# SingleSide.net
KiCad netlist of a schematic drawn in EAGLE
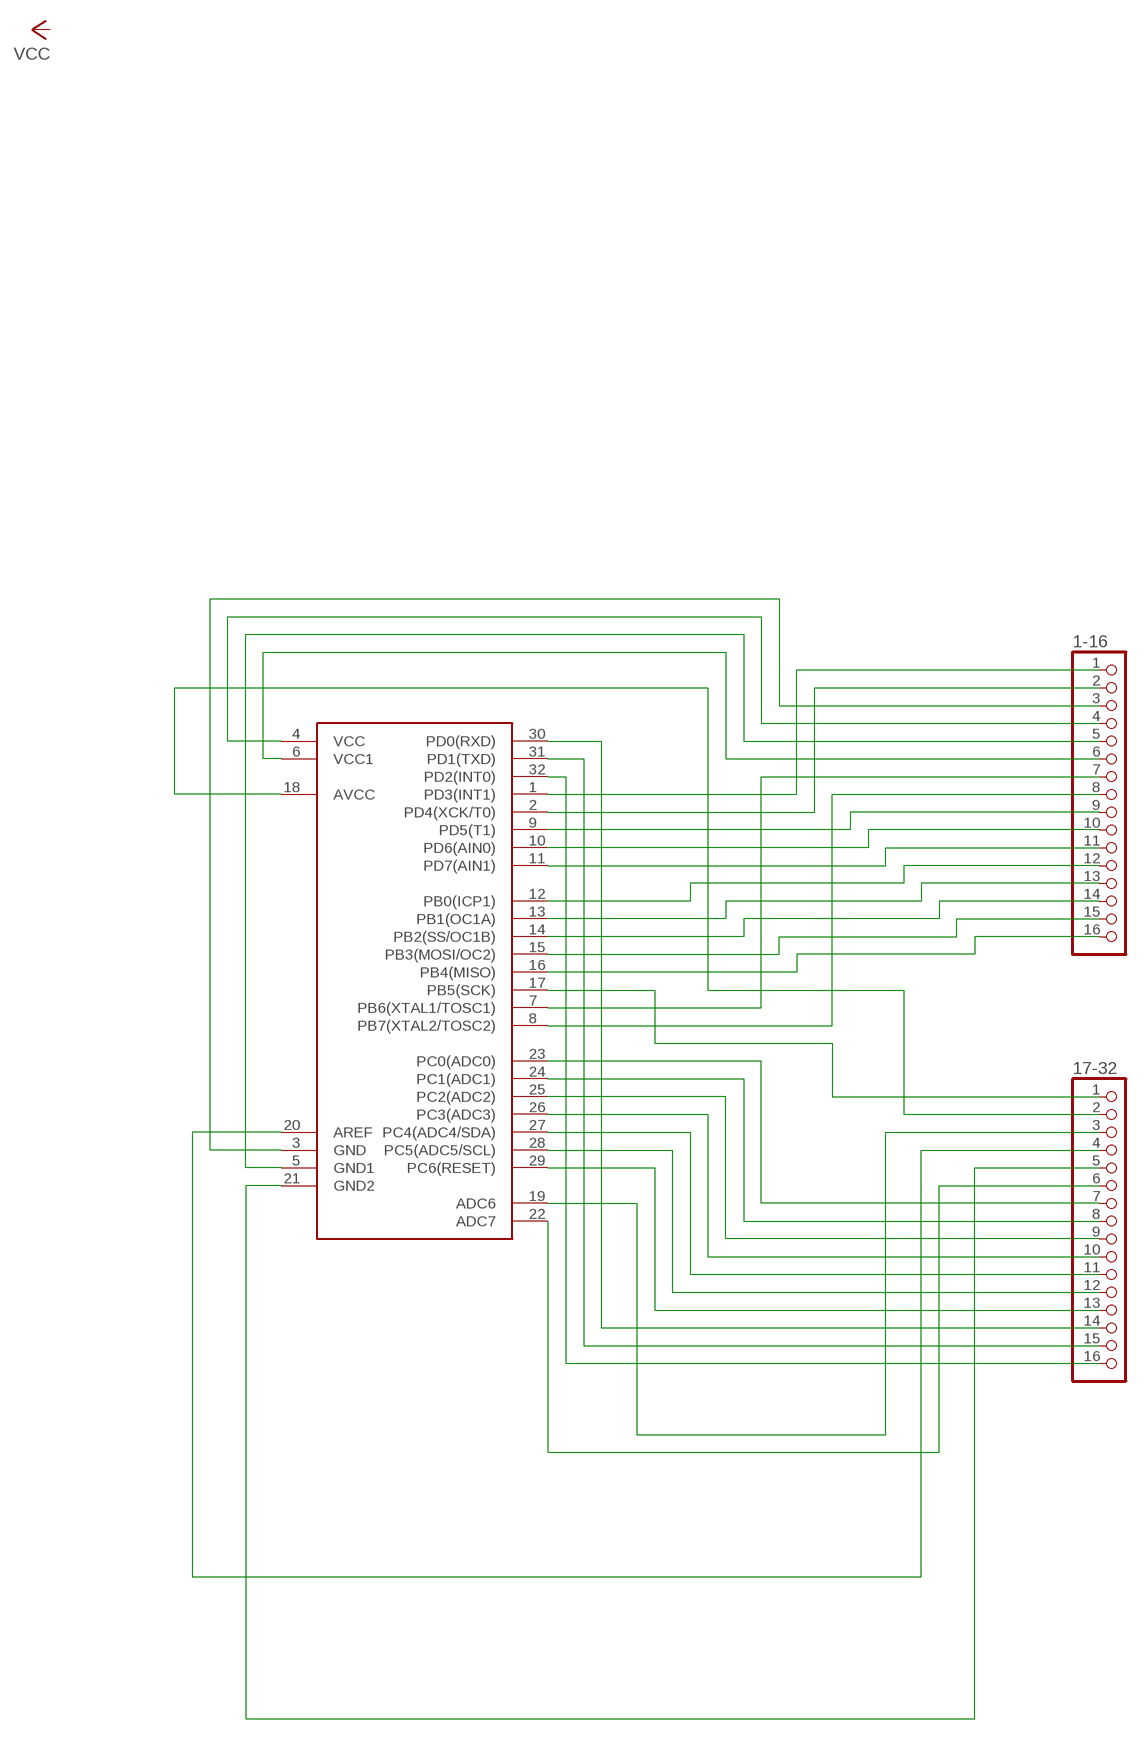
[diagram p0: schematic, sheet 1]

(export (version "E")
  (design (tool "Eeschema 10.0.6"))
  (components
    (comp (ref "1-16")
      (value "PINHD-1X16")
      (footprint "eagle-import:1X16")
      (libsource (lib "eagle-import") (part "PINHD-1X16"))
    )
    (comp (ref "17-32")
      (value "PINHD-1X16")
      (footprint "eagle-import:1X16")
      (libsource (lib "eagle-import") (part "PINHD-1X16"))
    )
    (comp (ref "U$1")
      (value "ATMEGA8A")
      (footprint "eagle-import:TQFP32-08")
      (libsource (lib "eagle-import") (part "ATMEGA8A"))
    )
  )
  (nets
    (net (code "1") (name "Net-(U$1-ADC6)") (class "Default")
      (node (ref "17-32") (pin "3") (pinfunction "3_3") (pintype "passive"))
      (node (ref "U$1") (pin "19") (pinfunction "ADC6_19") (pintype "bidirectional"))
    )
    (net (code "2") (name "Net-(U$1-ADC7)") (class "Default")
      (node (ref "17-32") (pin "6") (pinfunction "6_6") (pintype "passive"))
      (node (ref "U$1") (pin "22") (pinfunction "ADC7_22") (pintype "bidirectional"))
    )
    (net (code "3") (name "Net-(U$1-AREF)") (class "Default")
      (node (ref "17-32") (pin "4") (pinfunction "4_4") (pintype "passive"))
      (node (ref "U$1") (pin "20") (pinfunction "AREF_20") (pintype "bidirectional"))
    )
    (net (code "4") (name "Net-(U$1-AVCC)") (class "Default")
      (node (ref "17-32") (pin "2") (pinfunction "2_2") (pintype "passive"))
      (node (ref "U$1") (pin "18") (pinfunction "AVCC_18") (pintype "bidirectional"))
    )
    (net (code "5") (name "Net-(U$1-GND)") (class "Default")
      (node (ref "1-16") (pin "3") (pinfunction "3_3") (pintype "passive"))
      (node (ref "U$1") (pin "3") (pinfunction "GND_3") (pintype "bidirectional"))
    )
    (net (code "6") (name "Net-(U$1-GND1)") (class "Default")
      (node (ref "1-16") (pin "5") (pinfunction "5_5") (pintype "passive"))
      (node (ref "U$1") (pin "5") (pinfunction "GND1_5") (pintype "bidirectional"))
    )
    (net (code "7") (name "Net-(U$1-GND2)") (class "Default")
      (node (ref "17-32") (pin "5") (pinfunction "5_5") (pintype "passive"))
      (node (ref "U$1") (pin "21") (pinfunction "GND2_21") (pintype "bidirectional"))
    )
    (net (code "8") (name "Net-(U$1-PB0(ICP1))") (class "Default")
      (node (ref "1-16") (pin "12") (pinfunction "12_12") (pintype "passive"))
      (node (ref "U$1") (pin "12") (pinfunction "PB0(ICP1)_12") (pintype "bidirectional"))
    )
    (net (code "9") (name "Net-(U$1-PB1(OC1A))") (class "Default")
      (node (ref "1-16") (pin "13") (pinfunction "13_13") (pintype "passive"))
      (node (ref "U$1") (pin "13") (pinfunction "PB1(OC1A)_13") (pintype "bidirectional"))
    )
    (net (code "10") (name "Net-(U$1-PB2(SS{slash}OC1B))") (class "Default")
      (node (ref "1-16") (pin "14") (pinfunction "14_14") (pintype "passive"))
      (node (ref "U$1") (pin "14") (pinfunction "PB2(SS/OC1B)_14") (pintype "bidirectional"))
    )
    (net (code "11") (name "Net-(U$1-PB3(MOSI{slash}OC2))") (class "Default")
      (node (ref "1-16") (pin "15") (pinfunction "15_15") (pintype "passive"))
      (node (ref "U$1") (pin "15") (pinfunction "PB3(MOSI/OC2)_15") (pintype "bidirectional"))
    )
    (net (code "12") (name "Net-(U$1-PB4(MISO))") (class "Default")
      (node (ref "1-16") (pin "16") (pinfunction "16_16") (pintype "passive"))
      (node (ref "U$1") (pin "16") (pinfunction "PB4(MISO)_16") (pintype "bidirectional"))
    )
    (net (code "13") (name "Net-(U$1-PB5(SCK))") (class "Default")
      (node (ref "17-32") (pin "1") (pinfunction "1_1") (pintype "passive"))
      (node (ref "U$1") (pin "17") (pinfunction "PB5(SCK)_17") (pintype "bidirectional"))
    )
    (net (code "14") (name "Net-(U$1-PB6(XTAL1{slash}TOSC1))") (class "Default")
      (node (ref "1-16") (pin "7") (pinfunction "7_7") (pintype "passive"))
      (node (ref "U$1") (pin "7") (pinfunction "PB6(XTAL1/TOSC1)_7") (pintype "bidirectional"))
    )
    (net (code "15") (name "Net-(U$1-PB7(XTAL2{slash}TOSC2))") (class "Default")
      (node (ref "1-16") (pin "8") (pinfunction "8_8") (pintype "passive"))
      (node (ref "U$1") (pin "8") (pinfunction "PB7(XTAL2/TOSC2)_8") (pintype "bidirectional"))
    )
    (net (code "16") (name "Net-(U$1-PC0(ADC0))") (class "Default")
      (node (ref "17-32") (pin "7") (pinfunction "7_7") (pintype "passive"))
      (node (ref "U$1") (pin "23") (pinfunction "PC0(ADC0)_23") (pintype "bidirectional"))
    )
    (net (code "17") (name "Net-(U$1-PC1(ADC1))") (class "Default")
      (node (ref "17-32") (pin "8") (pinfunction "8_8") (pintype "passive"))
      (node (ref "U$1") (pin "24") (pinfunction "PC1(ADC1)_24") (pintype "bidirectional"))
    )
    (net (code "18") (name "Net-(U$1-PC2(ADC2))") (class "Default")
      (node (ref "17-32") (pin "9") (pinfunction "9_9") (pintype "passive"))
      (node (ref "U$1") (pin "25") (pinfunction "PC2(ADC2)_25") (pintype "bidirectional"))
    )
    (net (code "19") (name "Net-(U$1-PC3(ADC3))") (class "Default")
      (node (ref "17-32") (pin "10") (pinfunction "10_10") (pintype "passive"))
      (node (ref "U$1") (pin "26") (pinfunction "PC3(ADC3)_26") (pintype "bidirectional"))
    )
    (net (code "20") (name "Net-(U$1-PC4(ADC4{slash}SDA))") (class "Default")
      (node (ref "17-32") (pin "11") (pinfunction "11_11") (pintype "passive"))
      (node (ref "U$1") (pin "27") (pinfunction "PC4(ADC4/SDA)_27") (pintype "bidirectional"))
    )
    (net (code "21") (name "Net-(U$1-PC5(ADC5{slash}SCL))") (class "Default")
      (node (ref "17-32") (pin "12") (pinfunction "12_12") (pintype "passive"))
      (node (ref "U$1") (pin "28") (pinfunction "PC5(ADC5/SCL)_28") (pintype "bidirectional"))
    )
    (net (code "22") (name "Net-(U$1-PC6(RESET))") (class "Default")
      (node (ref "17-32") (pin "13") (pinfunction "13_13") (pintype "passive"))
      (node (ref "U$1") (pin "29") (pinfunction "PC6(RESET)_29") (pintype "bidirectional"))
    )
    (net (code "23") (name "Net-(U$1-PD0(RXD))") (class "Default")
      (node (ref "17-32") (pin "14") (pinfunction "14_14") (pintype "passive"))
      (node (ref "U$1") (pin "30") (pinfunction "PD0(RXD)_30") (pintype "bidirectional"))
    )
    (net (code "24") (name "Net-(U$1-PD1(TXD))") (class "Default")
      (node (ref "17-32") (pin "15") (pinfunction "15_15") (pintype "passive"))
      (node (ref "U$1") (pin "31") (pinfunction "PD1(TXD)_31") (pintype "bidirectional"))
    )
    (net (code "25") (name "Net-(U$1-PD2(INT0))") (class "Default")
      (node (ref "17-32") (pin "16") (pinfunction "16_16") (pintype "passive"))
      (node (ref "U$1") (pin "32") (pinfunction "PD2(INT0)_32") (pintype "bidirectional"))
    )
    (net (code "26") (name "Net-(U$1-PD3(INT1))") (class "Default")
      (node (ref "1-16") (pin "1") (pinfunction "1_1") (pintype "passive"))
      (node (ref "U$1") (pin "1") (pinfunction "PD3(INT1)_1") (pintype "bidirectional"))
    )
    (net (code "27") (name "Net-(U$1-PD4(XCK{slash}T0))") (class "Default")
      (node (ref "1-16") (pin "2") (pinfunction "2_2") (pintype "passive"))
      (node (ref "U$1") (pin "2") (pinfunction "PD4(XCK/T0)_2") (pintype "bidirectional"))
    )
    (net (code "28") (name "Net-(U$1-PD5(T1))") (class "Default")
      (node (ref "1-16") (pin "9") (pinfunction "9_9") (pintype "passive"))
      (node (ref "U$1") (pin "9") (pinfunction "PD5(T1)_9") (pintype "bidirectional"))
    )
    (net (code "29") (name "Net-(U$1-PD6(AIN0))") (class "Default")
      (node (ref "1-16") (pin "10") (pinfunction "10_10") (pintype "passive"))
      (node (ref "U$1") (pin "10") (pinfunction "PD6(AIN0)_10") (pintype "bidirectional"))
    )
    (net (code "30") (name "Net-(U$1-PD7(AIN1))") (class "Default")
      (node (ref "1-16") (pin "11") (pinfunction "11_11") (pintype "passive"))
      (node (ref "U$1") (pin "11") (pinfunction "PD7(AIN1)_11") (pintype "bidirectional"))
    )
    (net (code "31") (name "Net-(U$1-VCC)") (class "Default")
      (node (ref "1-16") (pin "4") (pinfunction "4_4") (pintype "passive"))
      (node (ref "U$1") (pin "4") (pinfunction "VCC_4") (pintype "bidirectional"))
    )
    (net (code "32") (name "Net-(U$1-VCC1)") (class "Default")
      (node (ref "1-16") (pin "6") (pinfunction "6_6") (pintype "passive"))
      (node (ref "U$1") (pin "6") (pinfunction "VCC1_6") (pintype "bidirectional"))
    )
  )
)
